# driver.net
KiCad netlist of a schematic drawn in EAGLE
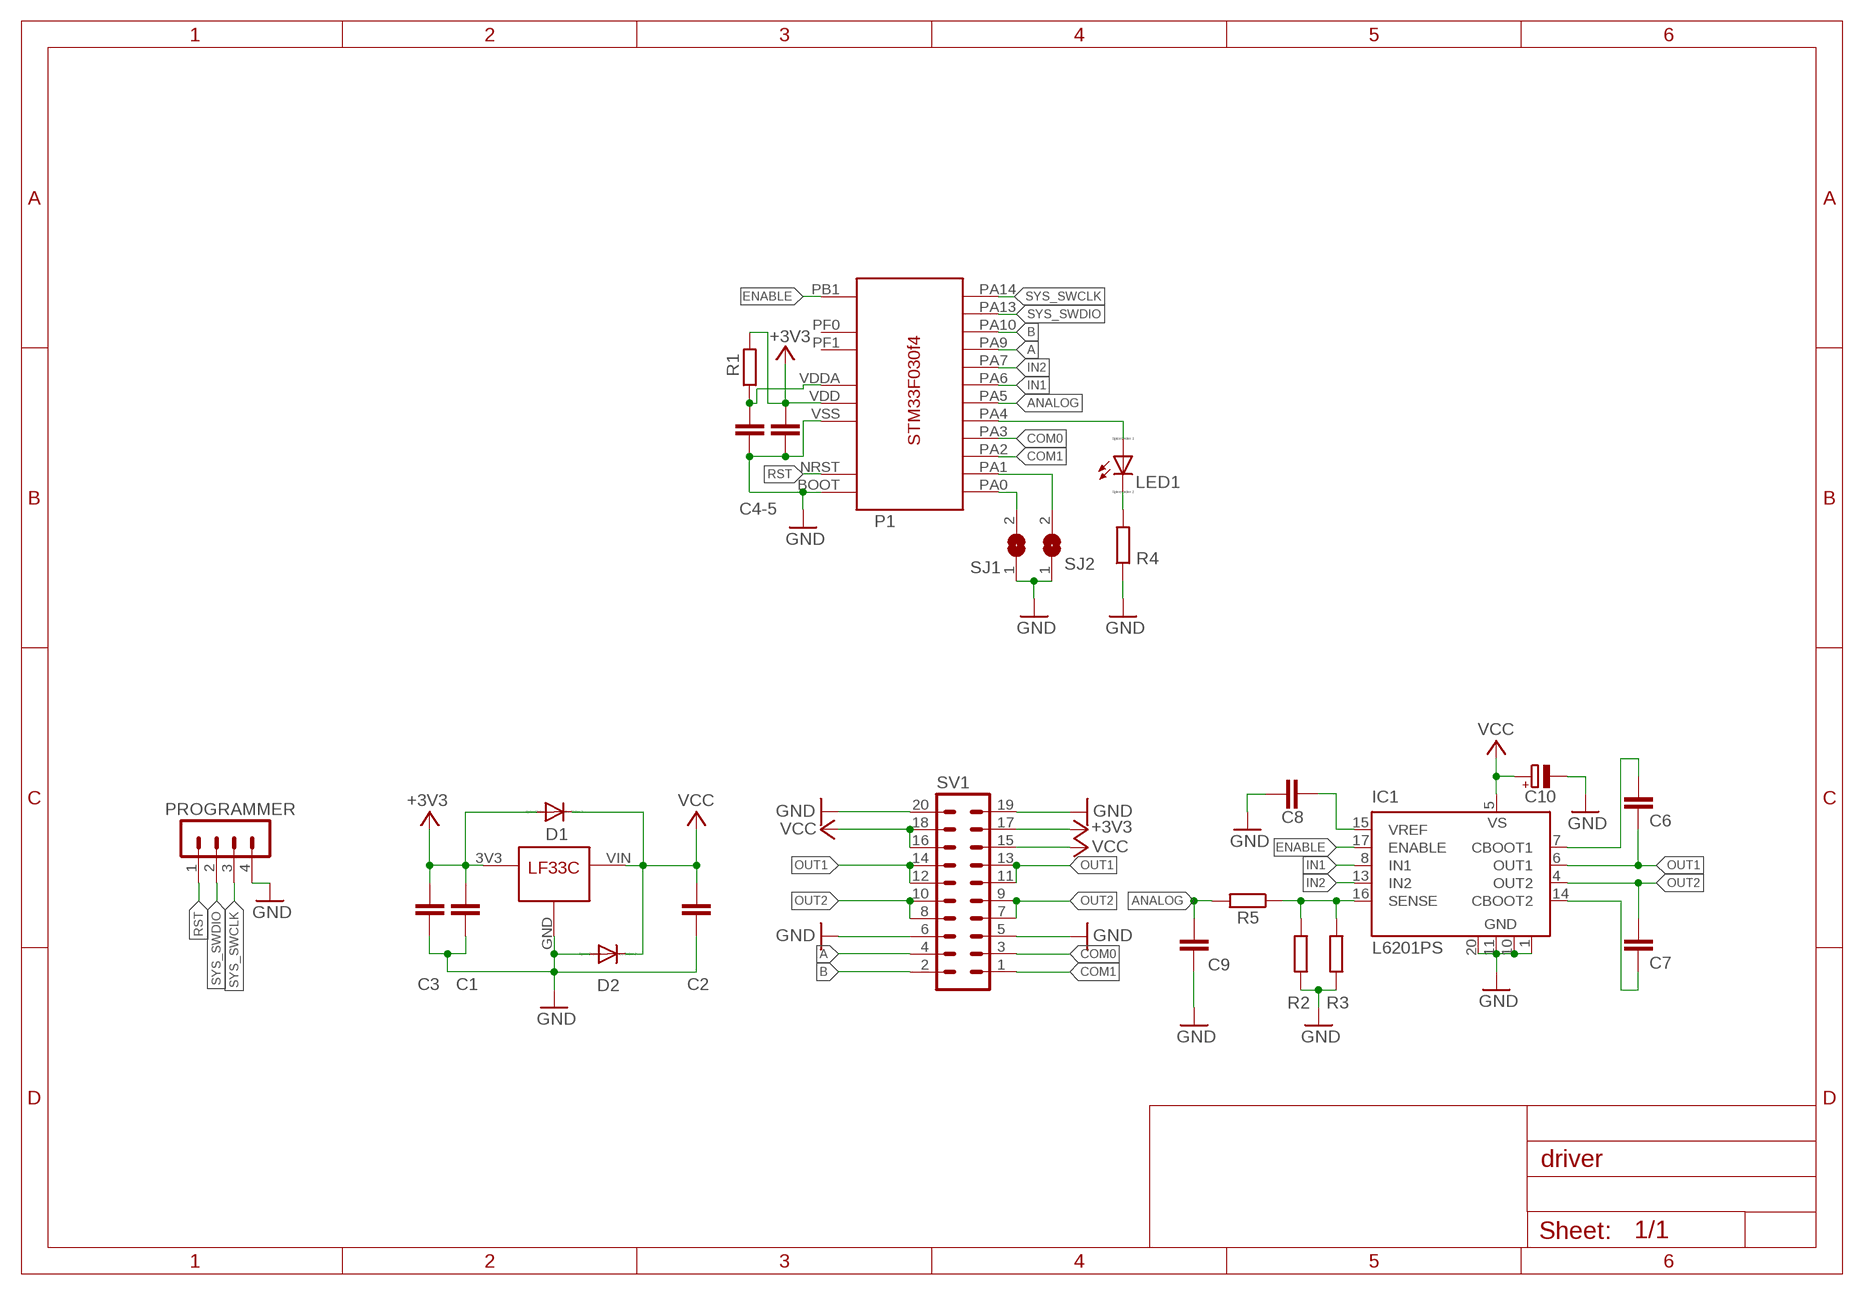
[diagram p0: schematic, sheet 1]

(export (version "E")
  (design (tool "Eeschema 10.0.6"))
  (components
    (comp (ref "C1")
      (value "220k")
      (footprint "eagle-import:C0603")
      (libsource (lib "eagle-import") (part "C-EUC0603"))
    )
    (comp (ref "C2")
      (value "220k")
      (footprint "eagle-import:C0603")
      (libsource (lib "eagle-import") (part "C-EUC0603"))
    )
    (comp (ref "C3")
      (value "10u")
      (footprint "eagle-import:C1206")
      (libsource (lib "eagle-import") (part "C-EUC1206"))
    )
    (comp (ref "C4")
      (value "100K")
      (footprint "eagle-import:C0603")
      (libsource (lib "eagle-import") (part "C-EUC0603"))
    )
    (comp (ref "C5")
      (value "100K")
      (footprint "eagle-import:C0603")
      (libsource (lib "eagle-import") (part "C-EUC0603"))
    )
    (comp (ref "C6")
      (value "15K")
      (footprint "eagle-import:C0603")
      (libsource (lib "eagle-import") (part "C-EUC0603"))
    )
    (comp (ref "C7")
      (value "15K")
      (footprint "eagle-import:C0603")
      (libsource (lib "eagle-import") (part "C-EUC0603"))
    )
    (comp (ref "C8")
      (value "220k")
      (footprint "eagle-import:C0603")
      (libsource (lib "eagle-import") (part "C-EUC0603"))
    )
    (comp (ref "C9")
      (value "220k")
      (footprint "eagle-import:C0603")
      (libsource (lib "eagle-import") (part "C-EUC0603"))
    )
    (comp (ref "C10")
      (value "CPOL-EUD/7343-31W")
      (footprint "eagle-import:D_7343-31W")
      (libsource (lib "eagle-import") (part "CPOL-EUD/7343-31W"))
    )
    (comp (ref "D1")
      (value "DIODE-MINIMELF")
      (footprint "eagle-import:MINIMELF")
      (libsource (lib "eagle-import") (part "DIODE-MINIMELF"))
    )
    (comp (ref "D2")
      (value "DIODE-MINIMELF")
      (footprint "eagle-import:MINIMELF")
      (libsource (lib "eagle-import") (part "DIODE-MINIMELF"))
    )
    (comp (ref "IC1")
      (value "L6201PS")
      (footprint "eagle-import:POWERSO-20")
      (fields (field (name "MF") "Arrow Electronics"))
      (libsource (lib "eagle-import") (part "L6201PS"))
    )
    (comp (ref "LED1")
      (value "LED_E")
      (footprint "eagle-import:LED_1206")
      (libsource (lib "eagle-import") (part "LED_E"))
    )
    (comp (ref "P1")
      (value "STM32F030F4")
      (footprint "eagle-import:STM32F030F4")
      (libsource (lib "eagle-import") (part "STM32F030F4"))
    )
    (comp (ref "PROGRAMMER")
      (value "MA04-1")
      (footprint "eagle-import:MA04-1")
      (libsource (lib "eagle-import") (part "MA04-1"))
    )
    (comp (ref "R1")
      (value "R-EU_R1206")
      (footprint "eagle-import:R1206")
      (libsource (lib "eagle-import") (part "R-EU_R1206"))
    )
    (comp (ref "R2")
      (value "R1")
      (footprint "eagle-import:R2512")
      (libsource (lib "eagle-import") (part "R-EU_R2512"))
    )
    (comp (ref "R3")
      (value "R1")
      (footprint "eagle-import:R2512")
      (libsource (lib "eagle-import") (part "R-EU_R2512"))
    )
    (comp (ref "R4")
      (value "R-EU_R0603")
      (footprint "eagle-import:R0603")
      (libsource (lib "eagle-import") (part "R-EU_R0603"))
    )
    (comp (ref "R5")
      (value "R-EU_R0603")
      (footprint "eagle-import:R0603")
      (libsource (lib "eagle-import") (part "R-EU_R0603"))
    )
    (comp (ref "SJ1") (value "SJ") (footprint "eagle-import:SJ") (libsource (lib "eagle-import") (part "SJ")))
    (comp (ref "SJ2") (value "SJ") (footprint "eagle-import:SJ") (libsource (lib "eagle-import") (part "SJ")))
    (comp (ref "SV1")
      (value "MA10-2W")
      (footprint "eagle-import:MA10-2W")
      (libsource (lib "eagle-import") (part "MA10-2W"))
    )
    (comp (ref "U$1")
      (value "LF33C")
      (footprint "eagle-import:LF33C")
      (libsource (lib "eagle-import") (part "LF33C"))
    )
  )
  (nets
    (net (code "1") (name "+3V3") (class "Default")
      (node (ref "C1") (pin "1") (pinfunction "1_1") (pintype "passive"))
      (node (ref "C3") (pin "1") (pinfunction "1_1") (pintype "passive"))
      (node (ref "C5") (pin "1") (pinfunction "1_1") (pintype "passive"))
      (node (ref "D1") (pin "A") (pinfunction "A_A") (pintype "passive"))
      (node (ref "P1") (pin "VDD") (pinfunction "VDD_VDD") (pintype "bidirectional"))
      (node (ref "R1") (pin "2") (pinfunction "2_2") (pintype "passive"))
      (node (ref "SV1") (pin "17") (pinfunction "17_17") (pintype "passive"))
      (node (ref "U$1") (pin "3V3") (pinfunction "3V3_3V3") (pintype "bidirectional"))
    )
    (net (code "2") (name "A") (class "Default")
      (node (ref "P1") (pin "PA9") (pinfunction "PA9_PA9") (pintype "bidirectional"))
      (node (ref "SV1") (pin "4") (pinfunction "4_4") (pintype "passive"))
    )
    (net (code "3") (name "ANALOG") (class "Default")
      (node (ref "C9") (pin "1") (pinfunction "1_1") (pintype "passive"))
      (node (ref "P1") (pin "PA5") (pinfunction "PA5_PA5") (pintype "bidirectional"))
      (node (ref "R5") (pin "2") (pinfunction "2_2") (pintype "passive"))
    )
    (net (code "4") (name "B") (class "Default")
      (node (ref "P1") (pin "PA10") (pinfunction "PA10_PA10") (pintype "bidirectional"))
      (node (ref "SV1") (pin "2") (pinfunction "2_2") (pintype "passive"))
    )
    (net (code "5") (name "COM0") (class "Default")
      (node (ref "P1") (pin "PA3") (pinfunction "PA3_PA3") (pintype "bidirectional"))
      (node (ref "SV1") (pin "3") (pinfunction "3_3") (pintype "passive"))
    )
    (net (code "6") (name "COM1") (class "Default")
      (node (ref "P1") (pin "PA2") (pinfunction "PA2_PA2") (pintype "bidirectional"))
      (node (ref "SV1") (pin "1") (pinfunction "1_1") (pintype "passive"))
    )
    (net (code "7") (name "ENABLE") (class "Default")
      (node (ref "IC1") (pin "17") (pinfunction "ENABLE_17") (pintype "input"))
      (node (ref "P1") (pin "PB1") (pinfunction "PB1_PB1") (pintype "bidirectional"))
    )
    (net (code "8") (name "GND") (class "Default")
      (node (ref "C1") (pin "2") (pinfunction "2_2") (pintype "passive"))
      (node (ref "C10") (pin "-") (pinfunction "-_-") (pintype "passive"))
      (node (ref "C2") (pin "2") (pinfunction "2_2") (pintype "passive"))
      (node (ref "C3") (pin "2") (pinfunction "2_2") (pintype "passive"))
      (node (ref "C4") (pin "2") (pinfunction "2_2") (pintype "passive"))
      (node (ref "C5") (pin "2") (pinfunction "2_2") (pintype "passive"))
      (node (ref "C8") (pin "2") (pinfunction "2_2") (pintype "passive"))
      (node (ref "C9") (pin "2") (pinfunction "2_2") (pintype "passive"))
      (node (ref "D2") (pin "A") (pinfunction "A_A") (pintype "passive"))
      (node (ref "IC1") (pin "1") (pinfunction "GND_1") (pintype "power_in"))
      (node (ref "IC1") (pin "10") (pinfunction "GND_10") (pintype "power_in"))
      (node (ref "IC1") (pin "11") (pinfunction "GND_11") (pintype "power_in"))
      (node (ref "IC1") (pin "20") (pinfunction "GND_20") (pintype "power_in"))
      (node (ref "P1") (pin "BOOT") (pinfunction "BOOT_BOOT") (pintype "bidirectional"))
      (node (ref "P1") (pin "VSS") (pinfunction "VSS_VSS") (pintype "bidirectional"))
      (node (ref "PROGRAMMER") (pin "4") (pinfunction "4_4") (pintype "passive"))
      (node (ref "R2") (pin "1") (pinfunction "1_1") (pintype "passive"))
      (node (ref "R3") (pin "1") (pinfunction "1_1") (pintype "passive"))
      (node (ref "R4") (pin "1") (pinfunction "1_1") (pintype "passive"))
      (node (ref "SJ1") (pin "1") (pinfunction "1_1") (pintype "passive"))
      (node (ref "SJ2") (pin "1") (pinfunction "1_1") (pintype "passive"))
      (node (ref "SV1") (pin "19") (pinfunction "19_19") (pintype "passive"))
      (node (ref "SV1") (pin "20") (pinfunction "20_20") (pintype "passive"))
      (node (ref "SV1") (pin "5") (pinfunction "5_5") (pintype "passive"))
      (node (ref "SV1") (pin "6") (pinfunction "6_6") (pintype "passive"))
      (node (ref "U$1") (pin "GND") (pinfunction "GND_GND") (pintype "bidirectional"))
    )
    (net (code "9") (name "IN1") (class "Default")
      (node (ref "IC1") (pin "8") (pinfunction "IN1_8") (pintype "input"))
      (node (ref "P1") (pin "PA6") (pinfunction "PA6_PA6") (pintype "bidirectional"))
    )
    (net (code "10") (name "IN2") (class "Default")
      (node (ref "IC1") (pin "13") (pinfunction "IN2_13") (pintype "input"))
      (node (ref "P1") (pin "PA7") (pinfunction "PA7_PA7") (pintype "bidirectional"))
    )
    (net (code "11") (name "Net-(C4-Pad1)") (class "Default")
      (node (ref "C4") (pin "1") (pinfunction "1_1") (pintype "passive"))
      (node (ref "P1") (pin "VDDA") (pinfunction "VDDA_VDDA") (pintype "bidirectional"))
      (node (ref "R1") (pin "1") (pinfunction "1_1") (pintype "passive"))
    )
    (net (code "12") (name "Net-(IC1-CBOOT1)") (class "Default")
      (node (ref "C6") (pin "1") (pinfunction "1_1") (pintype "passive"))
      (node (ref "IC1") (pin "7") (pinfunction "CBOOT1_7") (pintype "input"))
    )
    (net (code "13") (name "Net-(IC1-CBOOT2)") (class "Default")
      (node (ref "C7") (pin "2") (pinfunction "2_2") (pintype "passive"))
      (node (ref "IC1") (pin "14") (pinfunction "CBOOT2_14") (pintype "input"))
    )
    (net (code "14") (name "Net-(IC1-SENSE)") (class "Default")
      (node (ref "IC1") (pin "16") (pinfunction "SENSE_16") (pintype "input"))
      (node (ref "R2") (pin "2") (pinfunction "2_2") (pintype "passive"))
      (node (ref "R3") (pin "2") (pinfunction "2_2") (pintype "passive"))
      (node (ref "R5") (pin "1") (pinfunction "1_1") (pintype "passive"))
    )
    (net (code "15") (name "Net-(IC1-VREF)") (class "Default")
      (node (ref "C8") (pin "1") (pinfunction "1_1") (pintype "passive"))
      (node (ref "IC1") (pin "15") (pinfunction "VREF_15") (pintype "input"))
    )
    (net (code "16") (name "Net-(LED1-PadA)") (class "Default")
      (node (ref "LED1") (pin "A") (pinfunction "A_A") (pintype "passive"))
      (node (ref "P1") (pin "PA4") (pinfunction "PA4_PA4") (pintype "bidirectional"))
    )
    (net (code "17") (name "Net-(LED1-PadC)") (class "Default")
      (node (ref "LED1") (pin "C") (pinfunction "C_C") (pintype "passive"))
      (node (ref "R4") (pin "2") (pinfunction "2_2") (pintype "passive"))
    )
    (net (code "18") (name "Net-(P1-PadPA0)") (class "Default")
      (node (ref "P1") (pin "PA0") (pinfunction "PA0_PA0") (pintype "bidirectional"))
      (node (ref "SJ1") (pin "2") (pinfunction "2_2") (pintype "passive"))
    )
    (net (code "19") (name "Net-(P1-PadPA1)") (class "Default")
      (node (ref "P1") (pin "PA1") (pinfunction "PA1_PA1") (pintype "bidirectional"))
      (node (ref "SJ2") (pin "2") (pinfunction "2_2") (pintype "passive"))
    )
    (net (code "20") (name "OUT1") (class "Default")
      (node (ref "C6") (pin "2") (pinfunction "2_2") (pintype "passive"))
      (node (ref "IC1") (pin "6") (pinfunction "OUT1_6") (pintype "output"))
      (node (ref "SV1") (pin "11") (pinfunction "11_11") (pintype "passive"))
      (node (ref "SV1") (pin "12") (pinfunction "12_12") (pintype "passive"))
      (node (ref "SV1") (pin "13") (pinfunction "13_13") (pintype "passive"))
      (node (ref "SV1") (pin "14") (pinfunction "14_14") (pintype "passive"))
    )
    (net (code "21") (name "OUT2") (class "Default")
      (node (ref "C7") (pin "1") (pinfunction "1_1") (pintype "passive"))
      (node (ref "IC1") (pin "4") (pinfunction "OUT2_4") (pintype "output"))
      (node (ref "SV1") (pin "10") (pinfunction "10_10") (pintype "passive"))
      (node (ref "SV1") (pin "7") (pinfunction "7_7") (pintype "passive"))
      (node (ref "SV1") (pin "8") (pinfunction "8_8") (pintype "passive"))
      (node (ref "SV1") (pin "9") (pinfunction "9_9") (pintype "passive"))
    )
    (net (code "22") (name "RST") (class "Default")
      (node (ref "P1") (pin "NRST") (pinfunction "NRST_NRST") (pintype "bidirectional"))
      (node (ref "PROGRAMMER") (pin "1") (pinfunction "1_1") (pintype "passive"))
    )
    (net (code "23") (name "SYS_SWCLK") (class "Default")
      (node (ref "P1") (pin "PA14") (pinfunction "PA14_PA14") (pintype "bidirectional"))
      (node (ref "PROGRAMMER") (pin "3") (pinfunction "3_3") (pintype "passive"))
    )
    (net (code "24") (name "SYS_SWDIO") (class "Default")
      (node (ref "P1") (pin "PA13") (pinfunction "PA13_PA13") (pintype "bidirectional"))
      (node (ref "PROGRAMMER") (pin "2") (pinfunction "2_2") (pintype "passive"))
    )
    (net (code "25") (name "VCC") (class "Default")
      (node (ref "C10") (pin "+") (pinfunction "+_+") (pintype "passive"))
      (node (ref "C2") (pin "1") (pinfunction "1_1") (pintype "passive"))
      (node (ref "D1") (pin "C") (pinfunction "C_C") (pintype "passive"))
      (node (ref "D2") (pin "C") (pinfunction "C_C") (pintype "passive"))
      (node (ref "IC1") (pin "5") (pinfunction "VS_5") (pintype "power_in"))
      (node (ref "SV1") (pin "15") (pinfunction "15_15") (pintype "passive"))
      (node (ref "SV1") (pin "16") (pinfunction "16_16") (pintype "passive"))
      (node (ref "SV1") (pin "18") (pinfunction "18_18") (pintype "passive"))
      (node (ref "U$1") (pin "VIN") (pinfunction "VIN_VIN") (pintype "bidirectional"))
    )
    (net (code "26") (name "unconnected-(P1-PadPF0)") (class "Default")
      (node (ref "P1") (pin "PF0") (pinfunction "PF0_PF0") (pintype "bidirectional"))
    )
    (net (code "27") (name "unconnected-(P1-PadPF1)") (class "Default")
      (node (ref "P1") (pin "PF1") (pinfunction "PF1_PF1") (pintype "bidirectional"))
    )
  )
)
